# PF8_AudioOutput.net
KiCad netlist of a schematic drawn in Altium Designer
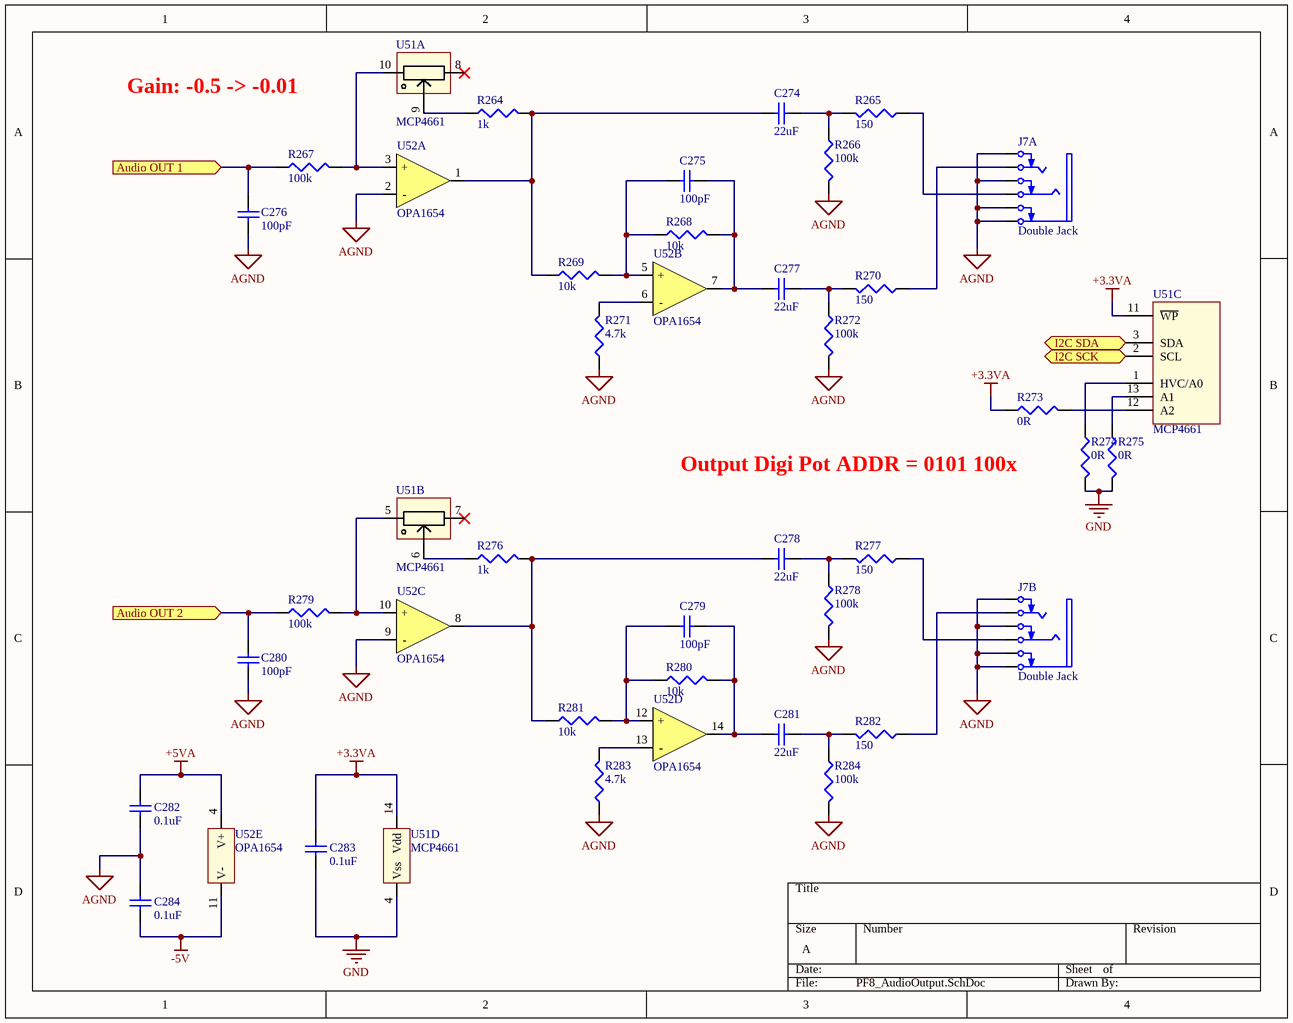
[diagram p0: PF8_AudioOutput.SchDoc]

(export (version "E")
  (design (tool "Eeschema 10.0.6"))
  (components
    (comp (ref "C274")
      (value "22uF")
      (footprint "CAPC1608X08")
      (description "Capacitor (Semiconductor SIM Model)")
      (libsource (lib "Michel") (part "Cap Semi"))
    )
    (comp (ref "C275")
      (value "100pF")
      (footprint "CAPC1608X08")
      (description "Capacitor (Semiconductor SIM Model)")
      (libsource (lib "Michel") (part "Cap Semi"))
    )
    (comp (ref "C276")
      (value "100pF")
      (footprint "CAPC1608X08")
      (description "Capacitor (Semiconductor SIM Model)")
      (libsource (lib "Michel") (part "Cap Semi"))
    )
    (comp (ref "C277")
      (value "22uF")
      (footprint "CAPC1608X08")
      (description "Capacitor (Semiconductor SIM Model)")
      (libsource (lib "Michel") (part "Cap Semi"))
    )
    (comp (ref "C278")
      (value "22uF")
      (footprint "CAPC1608X08")
      (description "Capacitor (Semiconductor SIM Model)")
      (libsource (lib "Michel") (part "Cap Semi"))
    )
    (comp (ref "C279")
      (value "100pF")
      (footprint "CAPC1608X08")
      (description "Capacitor (Semiconductor SIM Model)")
      (libsource (lib "Michel") (part "Cap Semi"))
    )
    (comp (ref "C280")
      (value "100pF")
      (footprint "CAPC1608X08")
      (description "Capacitor (Semiconductor SIM Model)")
      (libsource (lib "Michel") (part "Cap Semi"))
    )
    (comp (ref "C281")
      (value "22uF")
      (footprint "CAPC1608X08")
      (description "Capacitor (Semiconductor SIM Model)")
      (libsource (lib "Michel") (part "Cap Semi"))
    )
    (comp (ref "C282")
      (value "0.1uF")
      (footprint "CAPC1608X08")
      (description "Capacitor (Semiconductor SIM Model)")
      (libsource (lib "Michel") (part "Cap Semi"))
    )
    (comp (ref "C283")
      (value "0.1uF")
      (footprint "CAPC1608X08")
      (description "Capacitor (Semiconductor SIM Model)")
      (libsource (lib "Michel") (part "Cap Semi"))
    )
    (comp (ref "C284")
      (value "0.1uF")
      (footprint "CAPC1608X08")
      (description "Capacitor (Semiconductor SIM Model)")
      (libsource (lib "Michel") (part "Cap Semi"))
    )
    (comp (ref "J7")
      (value "Double Jack")
      (footprint "Amphenol_ACJS-MHDC")
      (description "Dual Jack stereo bypassed")
      (libsource (lib "Michel") (part "Dual TRS Jack Bypassed"))
    )
    (comp (ref "R264")
      (value "1k")
      (footprint "RESC1608X05")
      (description "Resistor")
      (libsource (lib "Michel") (part "Res3"))
    )
    (comp (ref "R265")
      (value "150")
      (footprint "RESC1608X05")
      (description "Resistor")
      (libsource (lib "Michel") (part "Res3"))
    )
    (comp (ref "R266")
      (value "100k")
      (footprint "RESC1608X05")
      (description "Resistor")
      (libsource (lib "Michel") (part "Res3"))
    )
    (comp (ref "R267")
      (value "100k")
      (footprint "RESC1608X05")
      (description "Resistor")
      (libsource (lib "Michel") (part "Res3"))
    )
    (comp (ref "R268")
      (value "10k")
      (footprint "RESC1608X05")
      (description "Resistor")
      (libsource (lib "Michel") (part "Res3"))
    )
    (comp (ref "R269")
      (value "10k")
      (footprint "RESC1608X05")
      (description "Resistor")
      (libsource (lib "Michel") (part "Res3"))
    )
    (comp (ref "R270")
      (value "150")
      (footprint "RESC1608X05")
      (description "Resistor")
      (libsource (lib "Michel") (part "Res3"))
    )
    (comp (ref "R271")
      (value "4.7k")
      (footprint "RESC1608X05")
      (description "Resistor")
      (libsource (lib "Michel") (part "Res3"))
    )
    (comp (ref "R272")
      (value "100k")
      (footprint "RESC1608X05")
      (description "Resistor")
      (libsource (lib "Michel") (part "Res3"))
    )
    (comp (ref "R273")
      (value "0R")
      (footprint "RESC1608X05")
      (description "Resistor")
      (libsource (lib "Michel") (part "Res3"))
    )
    (comp (ref "R274")
      (value "0R")
      (footprint "RESC1608X05")
      (description "Resistor")
      (libsource (lib "Michel") (part "Res3"))
    )
    (comp (ref "R275")
      (value "0R")
      (footprint "RESC1608X05")
      (description "Resistor")
      (libsource (lib "Michel") (part "Res3"))
    )
    (comp (ref "R276")
      (value "1k")
      (footprint "RESC1608X05")
      (description "Resistor")
      (libsource (lib "Michel") (part "Res3"))
    )
    (comp (ref "R277")
      (value "150")
      (footprint "RESC1608X05")
      (description "Resistor")
      (libsource (lib "Michel") (part "Res3"))
    )
    (comp (ref "R278")
      (value "100k")
      (footprint "RESC1608X05")
      (description "Resistor")
      (libsource (lib "Michel") (part "Res3"))
    )
    (comp (ref "R279")
      (value "100k")
      (footprint "RESC1608X05")
      (description "Resistor")
      (libsource (lib "Michel") (part "Res3"))
    )
    (comp (ref "R280")
      (value "10k")
      (footprint "RESC1608X05")
      (description "Resistor")
      (libsource (lib "Michel") (part "Res3"))
    )
    (comp (ref "R281")
      (value "10k")
      (footprint "RESC1608X05")
      (description "Resistor")
      (libsource (lib "Michel") (part "Res3"))
    )
    (comp (ref "R282")
      (value "150")
      (footprint "RESC1608X05")
      (description "Resistor")
      (libsource (lib "Michel") (part "Res3"))
    )
    (comp (ref "R283")
      (value "4.7k")
      (footprint "RESC1608X05")
      (description "Resistor")
      (libsource (lib "Michel") (part "Res3"))
    )
    (comp (ref "R284")
      (value "100k")
      (footprint "RESC1608X05")
      (description "Resistor")
      (libsource (lib "Michel") (part "Res3"))
    )
    (comp (ref "U51")
      (value "MCP4661")
      (footprint "TSSOP14_MC-M")
      (description "Dual DigiPot non volatile I2C")
      (libsource (lib "") (part "MCP4661_1"))
    )
    (comp (ref "U52")
      (value "OPA1654")
      (footprint "D14-M")
      (description "Quad Audio OpAmp")
      (libsource (lib "Michel") (part "OPA1654"))
    )
  )
  (nets
    (net (code "1") (name "+3.3VA") (class "Default")
      (node (ref "C283") (pin "1") (pinfunction "1_1") (pintype "passive"))
      (node (ref "R273") (pin "1") (pinfunction "1_1") (pintype "passive"))
      (node (ref "U51") (pin "11") (pinfunction "~{WP}_11") (pintype "passive"))
      (node (ref "U51") (pin "14") (pinfunction "Vdd_14") (pintype "power_in"))
    )
    (net (code "2") (name "+5VA") (class "Default")
      (node (ref "C282") (pin "1") (pinfunction "1_1") (pintype "passive"))
      (node (ref "U52") (pin "4") (pinfunction "V+_4") (pintype "power_in"))
    )
    (net (code "3") (name "-5V") (class "Default")
      (node (ref "C284") (pin "2") (pinfunction "2_2") (pintype "passive"))
      (node (ref "U52") (pin "11") (pinfunction "V-_11") (pintype "power_in"))
    )
    (net (code "4") (name "/Audio OUT 1") (class "Default")
      (node (ref "C276") (pin "2") (pinfunction "2_2") (pintype "passive"))
      (node (ref "R267") (pin "1") (pinfunction "1_1") (pintype "passive"))
    )
    (net (code "5") (name "/Audio OUT 2") (class "Default")
      (node (ref "C280") (pin "2") (pinfunction "2_2") (pintype "passive"))
      (node (ref "R279") (pin "1") (pinfunction "1_1") (pintype "passive"))
    )
    (net (code "6") (name "/I2C SCK") (class "Default")
      (node (ref "U51") (pin "2") (pinfunction "SCL_2") (pintype "passive"))
    )
    (net (code "7") (name "/I2C SDA") (class "Default")
      (node (ref "U51") (pin "3") (pinfunction "SDA_3") (pintype "passive"))
    )
    (net (code "8") (name "AGND") (class "Default")
      (node (ref "C276") (pin "1") (pinfunction "1_1") (pintype "passive"))
      (node (ref "C280") (pin "1") (pinfunction "1_1") (pintype "passive"))
      (node (ref "C282") (pin "2") (pinfunction "2_2") (pintype "passive"))
      (node (ref "C284") (pin "1") (pinfunction "1_1") (pintype "passive"))
      (node (ref "J7") (pin "1") (pinfunction "SB_1") (pintype "passive"))
      (node (ref "J7") (pin "10") (pinfunction "S_10") (pintype "power_in"))
      (node (ref "J7") (pin "2") (pinfunction "RB_2") (pintype "passive"))
      (node (ref "J7") (pin "3") (pinfunction "TB_3") (pintype "passive"))
      (node (ref "J7") (pin "4") (pinfunction "S_4") (pintype "power_in"))
      (node (ref "J7") (pin "7") (pinfunction "SB_7") (pintype "passive"))
      (node (ref "J7") (pin "8") (pinfunction "RB_8") (pintype "passive"))
      (node (ref "J7") (pin "9") (pinfunction "TB_9") (pintype "passive"))
      (node (ref "R266") (pin "2") (pinfunction "2_2") (pintype "passive"))
      (node (ref "R271") (pin "1") (pinfunction "1_1") (pintype "passive"))
      (node (ref "R272") (pin "2") (pinfunction "2_2") (pintype "passive"))
      (node (ref "R278") (pin "2") (pinfunction "2_2") (pintype "passive"))
      (node (ref "R283") (pin "1") (pinfunction "1_1") (pintype "passive"))
      (node (ref "R284") (pin "2") (pinfunction "2_2") (pintype "passive"))
      (node (ref "U52") (pin "2") (pinfunction "-_2") (pintype "passive"))
      (node (ref "U52") (pin "9") (pinfunction "-_9") (pintype "passive"))
    )
    (net (code "9") (name "GND") (class "Default")
      (node (ref "C283") (pin "2") (pinfunction "2_2") (pintype "passive"))
      (node (ref "R274") (pin "2") (pinfunction "2_2") (pintype "passive"))
      (node (ref "R275") (pin "2") (pinfunction "2_2") (pintype "passive"))
      (node (ref "U51") (pin "4") (pinfunction "Vss_4") (pintype "power_in"))
    )
    (net (code "10") (name "Net-(C274-Pad1)") (class "Default")
      (node (ref "C274") (pin "1") (pinfunction "1_1") (pintype "passive"))
      (node (ref "R265") (pin "2") (pinfunction "2_2") (pintype "passive"))
      (node (ref "R266") (pin "1") (pinfunction "1_1") (pintype "passive"))
    )
    (net (code "11") (name "Net-(C277-Pad1)") (class "Default")
      (node (ref "C277") (pin "1") (pinfunction "1_1") (pintype "passive"))
      (node (ref "R270") (pin "2") (pinfunction "2_2") (pintype "passive"))
      (node (ref "R272") (pin "1") (pinfunction "1_1") (pintype "passive"))
    )
    (net (code "12") (name "Net-(C278-Pad1)") (class "Default")
      (node (ref "C278") (pin "1") (pinfunction "1_1") (pintype "passive"))
      (node (ref "R277") (pin "2") (pinfunction "2_2") (pintype "passive"))
      (node (ref "R278") (pin "1") (pinfunction "1_1") (pintype "passive"))
    )
    (net (code "13") (name "Net-(C281-Pad1)") (class "Default")
      (node (ref "C281") (pin "1") (pinfunction "1_1") (pintype "passive"))
      (node (ref "R282") (pin "2") (pinfunction "2_2") (pintype "passive"))
      (node (ref "R284") (pin "1") (pinfunction "1_1") (pintype "passive"))
    )
    (net (code "14") (name "Net-(J7A-R)") (class "Default")
      (node (ref "J7") (pin "11") (pinfunction "R_11") (pintype "passive"))
      (node (ref "R265") (pin "1") (pinfunction "1_1") (pintype "passive"))
    )
    (net (code "15") (name "Net-(J7A-T)") (class "Default")
      (node (ref "J7") (pin "12") (pinfunction "T_12") (pintype "passive"))
      (node (ref "R270") (pin "1") (pinfunction "1_1") (pintype "passive"))
    )
    (net (code "16") (name "Net-(J7B-R)") (class "Default")
      (node (ref "J7") (pin "5") (pinfunction "R_5") (pintype "passive"))
      (node (ref "R277") (pin "1") (pinfunction "1_1") (pintype "passive"))
    )
    (net (code "17") (name "Net-(J7B-T)") (class "Default")
      (node (ref "J7") (pin "6") (pinfunction "T_6") (pintype "passive"))
      (node (ref "R282") (pin "1") (pinfunction "1_1") (pintype "passive"))
    )
    (net (code "18") (name "Net-(U51A-P0B)") (class "Default")
      (node (ref "R267") (pin "2") (pinfunction "2_2") (pintype "passive"))
      (node (ref "U51") (pin "10") (pinfunction "P0B_10") (pintype "passive"))
      (node (ref "U52") (pin "3") (pinfunction "+_3") (pintype "passive"))
    )
    (net (code "19") (name "Net-(U51A-P0W)") (class "Default")
      (node (ref "R264") (pin "1") (pinfunction "1_1") (pintype "passive"))
      (node (ref "U51") (pin "9") (pinfunction "P0W_9") (pintype "passive"))
    )
    (net (code "20") (name "Net-(U51B-P1B)") (class "Default")
      (node (ref "R279") (pin "2") (pinfunction "2_2") (pintype "passive"))
      (node (ref "U51") (pin "5") (pinfunction "P1B_5") (pintype "passive"))
      (node (ref "U52") (pin "10") (pinfunction "+_10") (pintype "passive"))
    )
    (net (code "21") (name "Net-(U51B-P1W)") (class "Default")
      (node (ref "R276") (pin "1") (pinfunction "1_1") (pintype "passive"))
      (node (ref "U51") (pin "6") (pinfunction "P1W_6") (pintype "passive"))
    )
    (net (code "22") (name "Net-(U51C-A1)") (class "Default")
      (node (ref "R275") (pin "1") (pinfunction "1_1") (pintype "passive"))
      (node (ref "U51") (pin "13") (pinfunction "A1_13") (pintype "power_in"))
    )
    (net (code "23") (name "Net-(U51C-A2)") (class "Default")
      (node (ref "R273") (pin "2") (pinfunction "2_2") (pintype "passive"))
      (node (ref "U51") (pin "12") (pinfunction "A2_12") (pintype "power_in"))
    )
    (net (code "24") (name "Net-(U51C-HVC{slash}A0)") (class "Default")
      (node (ref "R274") (pin "1") (pinfunction "1_1") (pintype "passive"))
      (node (ref "U51") (pin "1") (pinfunction "HVC/A0_1") (pintype "power_in"))
    )
    (net (code "25") (name "Net-(U52A-OUT)") (class "Default")
      (node (ref "C274") (pin "2") (pinfunction "2_2") (pintype "passive"))
      (node (ref "R264") (pin "2") (pinfunction "2_2") (pintype "passive"))
      (node (ref "R269") (pin "1") (pinfunction "1_1") (pintype "passive"))
      (node (ref "U52") (pin "1") (pinfunction "OUT_1") (pintype "passive"))
    )
    (net (code "26") (name "Net-(U52B-+)") (class "Default")
      (node (ref "C275") (pin "2") (pinfunction "2_2") (pintype "passive"))
      (node (ref "R268") (pin "1") (pinfunction "1_1") (pintype "passive"))
      (node (ref "R269") (pin "2") (pinfunction "2_2") (pintype "passive"))
      (node (ref "U52") (pin "5") (pinfunction "+_5") (pintype "passive"))
    )
    (net (code "27") (name "Net-(U52B--)") (class "Default")
      (node (ref "R271") (pin "2") (pinfunction "2_2") (pintype "passive"))
      (node (ref "U52") (pin "6") (pinfunction "-_6") (pintype "passive"))
    )
    (net (code "28") (name "Net-(U52B-OUT)") (class "Default")
      (node (ref "C275") (pin "1") (pinfunction "1_1") (pintype "passive"))
      (node (ref "C277") (pin "2") (pinfunction "2_2") (pintype "passive"))
      (node (ref "R268") (pin "2") (pinfunction "2_2") (pintype "passive"))
      (node (ref "U52") (pin "7") (pinfunction "OUT_7") (pintype "passive"))
    )
    (net (code "29") (name "Net-(U52C-OUT)") (class "Default")
      (node (ref "C278") (pin "2") (pinfunction "2_2") (pintype "passive"))
      (node (ref "R276") (pin "2") (pinfunction "2_2") (pintype "passive"))
      (node (ref "R281") (pin "1") (pinfunction "1_1") (pintype "passive"))
      (node (ref "U52") (pin "8") (pinfunction "OUT_8") (pintype "passive"))
    )
    (net (code "30") (name "Net-(U52D-+)") (class "Default")
      (node (ref "C279") (pin "2") (pinfunction "2_2") (pintype "passive"))
      (node (ref "R280") (pin "1") (pinfunction "1_1") (pintype "passive"))
      (node (ref "R281") (pin "2") (pinfunction "2_2") (pintype "passive"))
      (node (ref "U52") (pin "12") (pinfunction "+_12") (pintype "passive"))
    )
    (net (code "31") (name "Net-(U52D--)") (class "Default")
      (node (ref "R283") (pin "2") (pinfunction "2_2") (pintype "passive"))
      (node (ref "U52") (pin "13") (pinfunction "-_13") (pintype "passive"))
    )
    (net (code "32") (name "Net-(U52D-OUT)") (class "Default")
      (node (ref "C279") (pin "1") (pinfunction "1_1") (pintype "passive"))
      (node (ref "C281") (pin "2") (pinfunction "2_2") (pintype "passive"))
      (node (ref "R280") (pin "2") (pinfunction "2_2") (pintype "passive"))
      (node (ref "U52") (pin "14") (pinfunction "OUT_14") (pintype "passive"))
    )
    (net (code "33") (name "unconnected-(U51A-P0A-Pad8)") (class "Default")
      (node (ref "U51") (pin "8") (pinfunction "P0A_8") (pintype "passive+no_connect"))
    )
    (net (code "34") (name "unconnected-(U51B-P1A-Pad7)") (class "Default")
      (node (ref "U51") (pin "7") (pinfunction "P1A_7") (pintype "passive+no_connect"))
    )
  )
)
